# Sheet1.net
KiCad netlist of a schematic drawn in Altium Designer
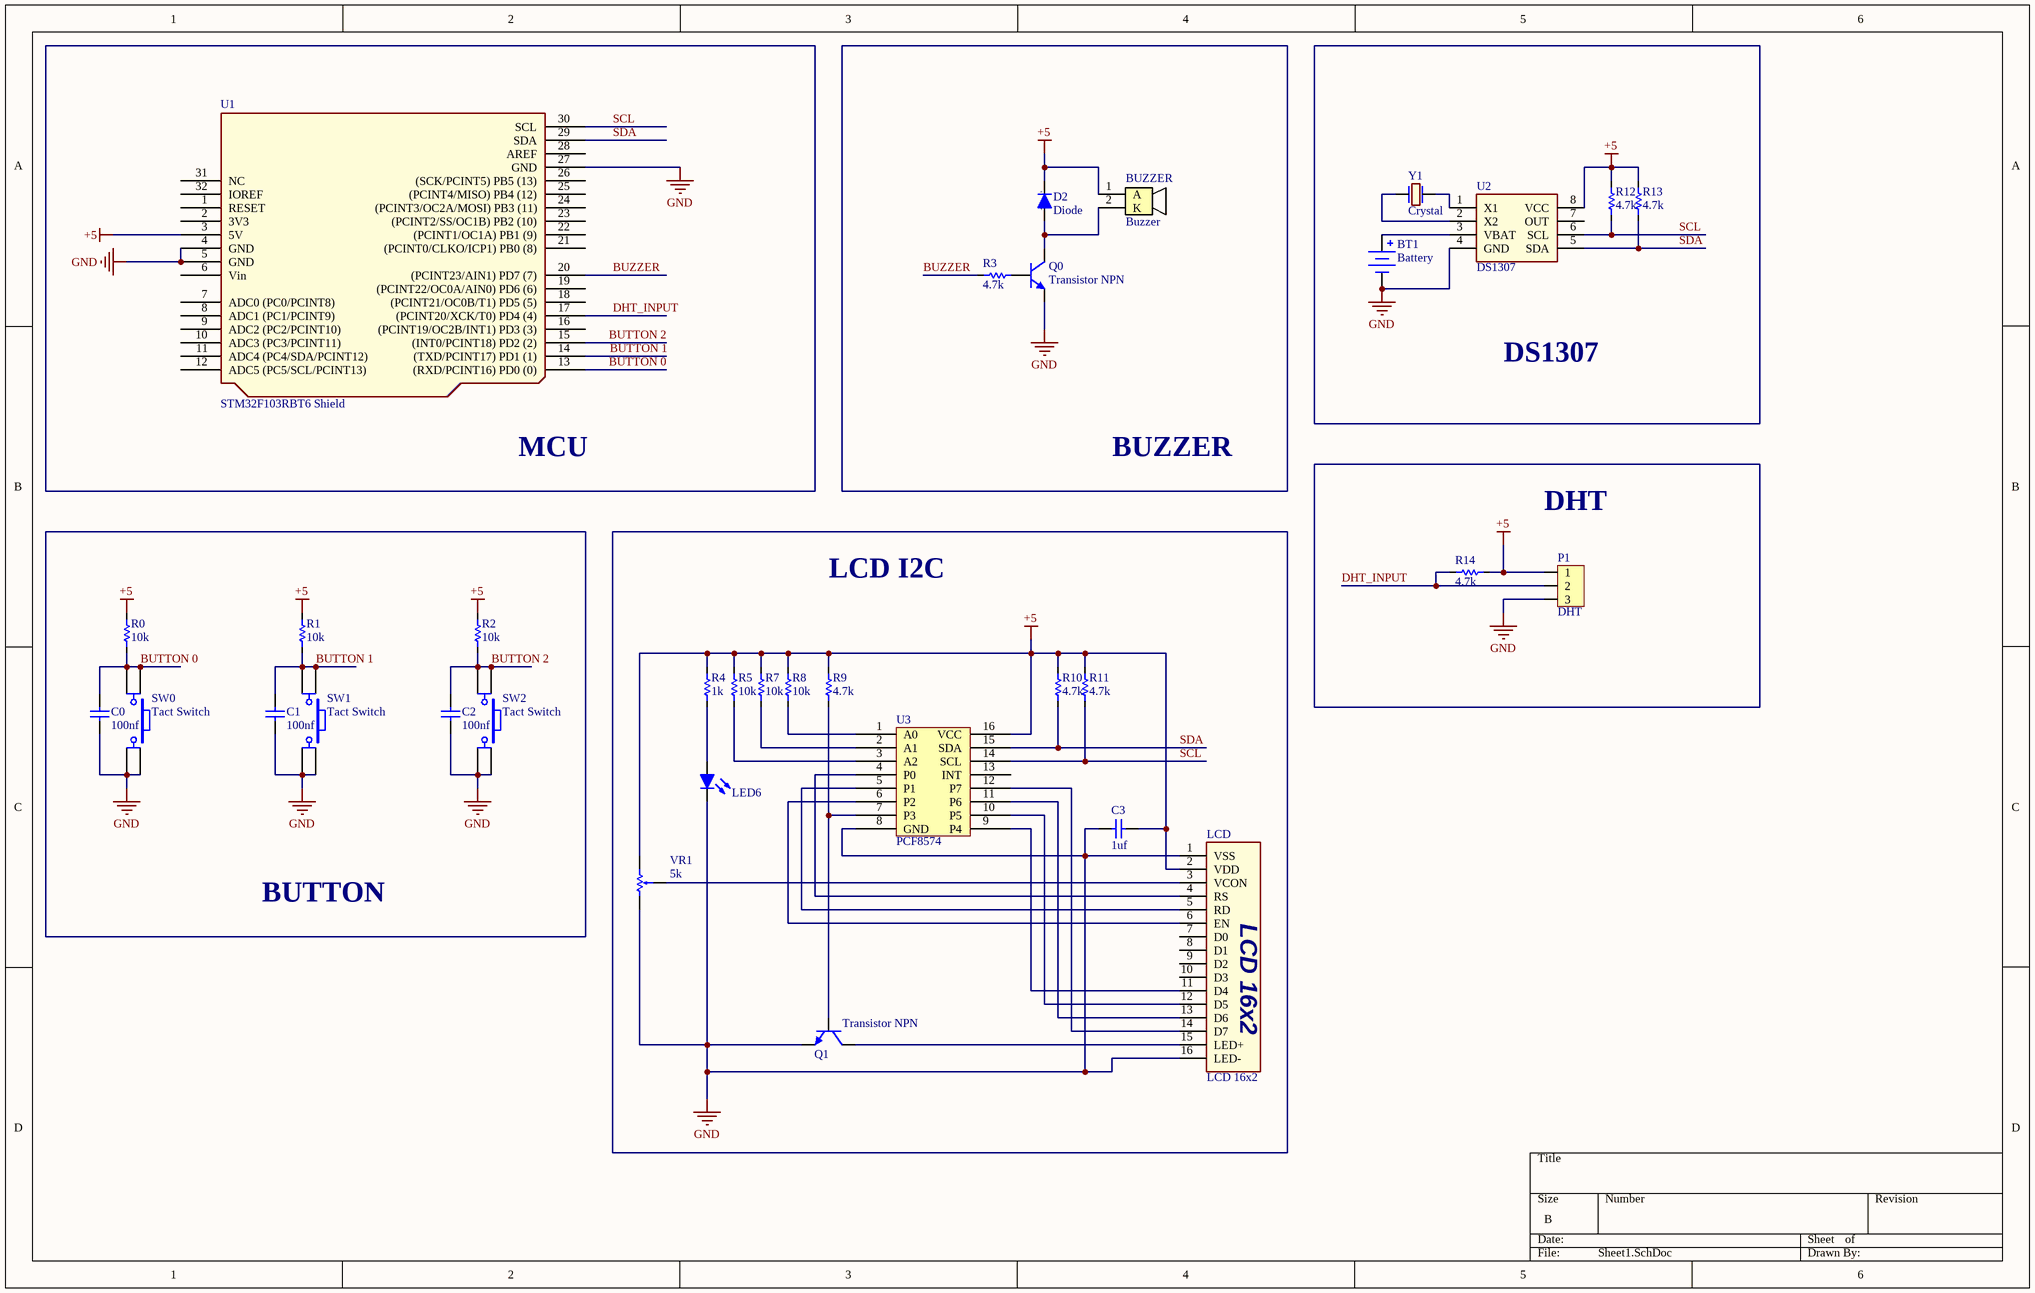
[diagram p0: Sheet1.SchDoc]

(export (version "E")
  (design (tool "Eeschema 10.0.6"))
  (components
    (comp (ref "BT1")
      (value "Battery")
      (footprint "CON CR2032")
      (libsource (lib "BKIT4U_LIB_NEW") (part "Battery"))
    )
    (comp (ref "BUZZER")
      (value "Buzzer")
      (footprint "BUZZER")
      (libsource (lib "BKIT4U_LIB_NEW") (part "Buzzer"))
    )
    (comp (ref "C0")
      (value "100nf")
      (footprint "C 0805 (2012)")
      (description "Capacitor non-pol")
      (libsource (lib "BKIT4U_LIB_NEW") (part "Capacitor NP"))
    )
    (comp (ref "C1")
      (value "100nf")
      (footprint "C 0805 (2012)")
      (description "Capacitor non-pol")
      (libsource (lib "BKIT4U_LIB_NEW") (part "Capacitor NP"))
    )
    (comp (ref "C2")
      (value "100nf")
      (footprint "C 0805 (2012)")
      (description "Capacitor non-pol")
      (libsource (lib "BKIT4U_LIB_NEW") (part "Capacitor NP"))
    )
    (comp (ref "C3")
      (value "1uf")
      (footprint "C 0805 (2012)")
      (description "Capacitor non-pol")
      (libsource (lib "BKIT4U_LIB_NEW") (part "Capacitor NP"))
    )
    (comp (ref "D2")
      (value "Diode")
      (footprint "SOD-80")
      (description "Default Diode")
      (fields (field (name "PUBLISHER") "Altium Limited"))
      (libsource (lib "BKIT4U_LIB_NEW") (part "Diode"))
    )
    (comp (ref "LCD")
      (value "LCD 16x2")
      (footprint "BKIT4U_LIB_NEW:LCD 16x2")
      (description "Character LCD 16x2")
      (libsource (lib "BKIT4U_LIB_NEW") (part "LCD 16x2"))
    )
    (comp (ref "LED6")
      (value "Led")
      (footprint "Led SMD 0805")
      (description "Typical LED")
      (libsource (lib "BKIT4U_LIB_NEW") (part "Led"))
    )
    (comp (ref "P1")
      (value "DHT")
      (footprint "XH2.54-3P")
      (description "Header, 3-Pin")
      (libsource (lib "BKIT4U_LIB_NEW") (part "Header 3"))
    )
    (comp (ref "Q0")
      (value "Transistor NPN")
      (footprint "SOT-23")
      (description "NPN Bipolar Transistor")
      (libsource (lib "BKIT4U_LIB_NEW") (part "Transistor NPN"))
    )
    (comp (ref "Q1")
      (value "Transistor NPN")
      (footprint "SOT-23")
      (description "NPN Bipolar Transistor")
      (libsource (lib "BKIT4U_LIB_NEW") (part "Transistor NPN"))
    )
    (comp (ref "R0")
      (value "10k")
      (footprint "R 0805 (2012)")
      (description "Resistor")
      (fields (field (name "PUBLISHER") "Altium Limited"))
      (libsource (lib "BKIT4U_LIB_NEW") (part "Resistor"))
    )
    (comp (ref "R1")
      (value "10k")
      (footprint "R 0805 (2012)")
      (description "Resistor")
      (fields (field (name "PUBLISHER") "Altium Limited"))
      (libsource (lib "BKIT4U_LIB_NEW") (part "Resistor"))
    )
    (comp (ref "R2")
      (value "10k")
      (footprint "R 0805 (2012)")
      (description "Resistor")
      (fields (field (name "PUBLISHER") "Altium Limited"))
      (libsource (lib "BKIT4U_LIB_NEW") (part "Resistor"))
    )
    (comp (ref "R3")
      (value "4.7k")
      (footprint "R 0805 (2012)")
      (description "Resistor")
      (fields (field (name "PUBLISHER") "Altium Limited"))
      (libsource (lib "BKIT4U_LIB_NEW") (part "Resistor"))
    )
    (comp (ref "R4")
      (value "1k")
      (footprint "R 0805 (2012)")
      (description "Resistor")
      (fields (field (name "PUBLISHER") "Altium Limited"))
      (libsource (lib "BKIT4U_LIB_NEW") (part "Resistor"))
    )
    (comp (ref "R5")
      (value "10k")
      (footprint "R 0805 (2012)")
      (description "Resistor")
      (fields (field (name "PUBLISHER") "Altium Limited"))
      (libsource (lib "BKIT4U_LIB_NEW") (part "Resistor"))
    )
    (comp (ref "R7")
      (value "10k")
      (footprint "R 0805 (2012)")
      (description "Resistor")
      (fields (field (name "PUBLISHER") "Altium Limited"))
      (libsource (lib "BKIT4U_LIB_NEW") (part "Resistor"))
    )
    (comp (ref "R8")
      (value "10k")
      (footprint "R 0805 (2012)")
      (description "Resistor")
      (fields (field (name "PUBLISHER") "Altium Limited"))
      (libsource (lib "BKIT4U_LIB_NEW") (part "Resistor"))
    )
    (comp (ref "R9")
      (value "4.7k")
      (footprint "R 0805 (2012)")
      (description "Resistor")
      (fields (field (name "PUBLISHER") "Altium Limited"))
      (libsource (lib "BKIT4U_LIB_NEW") (part "Resistor"))
    )
    (comp (ref "R10")
      (value "4.7k")
      (footprint "R 0805 (2012)")
      (description "Resistor")
      (fields (field (name "PUBLISHER") "Altium Limited"))
      (libsource (lib "BKIT4U_LIB_NEW") (part "Resistor"))
    )
    (comp (ref "R11")
      (value "4.7k")
      (footprint "R 0805 (2012)")
      (description "Resistor")
      (fields (field (name "PUBLISHER") "Altium Limited"))
      (libsource (lib "BKIT4U_LIB_NEW") (part "Resistor"))
    )
    (comp (ref "R12")
      (value "4.7k")
      (footprint "R 0805 (2012)")
      (description "Resistor")
      (fields (field (name "PUBLISHER") "Altium Limited"))
      (libsource (lib "BKIT4U_LIB_NEW") (part "Resistor"))
    )
    (comp (ref "R13")
      (value "4.7k")
      (footprint "R 0805 (2012)")
      (description "Resistor")
      (fields (field (name "PUBLISHER") "Altium Limited"))
      (libsource (lib "BKIT4U_LIB_NEW") (part "Resistor"))
    )
    (comp (ref "R14")
      (value "4.7k")
      (footprint "R 0805 (2012)")
      (description "Resistor")
      (fields (field (name "PUBLISHER") "Altium Limited"))
      (libsource (lib "BKIT4U_LIB_NEW") (part "Resistor"))
    )
    (comp (ref "SW0")
      (value "Tact Switch")
      (footprint "SW/4/DIP 12x12x7")
      (description "Tact switch 4 pin")
      (libsource (lib "BKIT4U_LIB_NEW") (part "SW SPST-4"))
    )
    (comp (ref "SW1")
      (value "Tact Switch")
      (footprint "SW/4/DIP 12x12x7")
      (description "Tact switch 4 pin")
      (libsource (lib "BKIT4U_LIB_NEW") (part "SW SPST-4"))
    )
    (comp (ref "SW2")
      (value "Tact Switch")
      (footprint "SW/4/DIP 12x12x7")
      (description "Tact switch 4 pin")
      (libsource (lib "BKIT4U_LIB_NEW") (part "SW SPST-4"))
    )
    (comp (ref "U1")
      (value "STM32F103RBT6 Shield")
      (footprint "Arduino Uno R3 Shield 2xPins")
      (description "Arduino Uno R3 shield pins connection")
      (libsource (lib "BKIT4U_LIB_NEW") (part "Arduino Uno R3 shield"))
    )
    (comp (ref "U2") (value "DS1307") (footprint "DIP 8") (libsource (lib "BKIT4U_LIB_NEW") (part "DS1307")))
    (comp (ref "U3")
      (value "PCF8574")
      (footprint "BKIT4U_LIB_NEW:SOIC-16")
      (description "Remote 8-Bit I/O Expander for I  2C Bus")
      (libsource (lib "Custom Library") (part "PCF8574"))
    )
    (comp (ref "VR1")
      (value "5k")
      (footprint "R Var 3mm")
      (description "Resistor Variable")
      (libsource (lib "chipfc_libs") (part "Resistor Variable"))
    )
    (comp (ref "Y1")
      (value "Crystal")
      (footprint "Crystal HC49US SMD")
      (libsource (lib "BKIT4U_LIB_NEW") (part "Crystal"))
    )
  )
  (nets
    (net (code "1") (name "+5") (class "Default")
      (node (ref "BUZZER") (pin "1") (pinfunction "A_1") (pintype "passive"))
      (node (ref "C3") (pin "2") (pinfunction "2_2") (pintype "passive"))
      (node (ref "D2") (pin "1") (pinfunction "Cathode_1") (pintype "passive"))
      (node (ref "LCD") (pin "2") (pinfunction "VDD_2") (pintype "passive"))
      (node (ref "P1") (pin "1") (pinfunction "1_1") (pintype "passive"))
      (node (ref "R0") (pin "2") (pinfunction "2_2") (pintype "passive"))
      (node (ref "R1") (pin "2") (pinfunction "2_2") (pintype "passive"))
      (node (ref "R10") (pin "2") (pinfunction "2_2") (pintype "passive"))
      (node (ref "R11") (pin "2") (pinfunction "2_2") (pintype "passive"))
      (node (ref "R12") (pin "2") (pinfunction "2_2") (pintype "passive"))
      (node (ref "R13") (pin "2") (pinfunction "2_2") (pintype "passive"))
      (node (ref "R14") (pin "1") (pinfunction "1_1") (pintype "passive"))
      (node (ref "R2") (pin "2") (pinfunction "2_2") (pintype "passive"))
      (node (ref "R4") (pin "2") (pinfunction "2_2") (pintype "passive"))
      (node (ref "R5") (pin "2") (pinfunction "2_2") (pintype "passive"))
      (node (ref "R7") (pin "2") (pinfunction "2_2") (pintype "passive"))
      (node (ref "R8") (pin "2") (pinfunction "2_2") (pintype "passive"))
      (node (ref "R9") (pin "2") (pinfunction "2_2") (pintype "passive"))
      (node (ref "U1") (pin "3") (pinfunction "5V_3") (pintype "passive"))
      (node (ref "U2") (pin "8") (pinfunction "VCC_8") (pintype "passive"))
      (node (ref "U3") (pin "16") (pinfunction "VCC_16") (pintype "passive"))
      (node (ref "VR1") (pin "1") (pinfunction "1_1") (pintype "passive"))
    )
    (net (code "2") (name "/BUTTON 0") (class "Default")
      (node (ref "C0") (pin "1") (pinfunction "1_1") (pintype "passive"))
      (node (ref "R0") (pin "1") (pinfunction "1_1") (pintype "passive"))
      (node (ref "SW0") (pin "1") (pinfunction "1_1") (pintype "passive"))
      (node (ref "SW0") (pin "4") (pinfunction "2_4") (pintype "passive"))
      (node (ref "U1") (pin "13") (pinfunction "(RXD/PCINT16)_PD0_(0)_13") (pintype "passive"))
    )
    (net (code "3") (name "/BUTTON 1") (class "Default")
      (node (ref "C1") (pin "1") (pinfunction "1_1") (pintype "passive"))
      (node (ref "R1") (pin "1") (pinfunction "1_1") (pintype "passive"))
      (node (ref "SW1") (pin "1") (pinfunction "1_1") (pintype "passive"))
      (node (ref "SW1") (pin "4") (pinfunction "2_4") (pintype "passive"))
      (node (ref "U1") (pin "14") (pinfunction "(TXD/PCINT17)_PD1_(1)_14") (pintype "passive"))
    )
    (net (code "4") (name "/BUTTON 2") (class "Default")
      (node (ref "C2") (pin "1") (pinfunction "1_1") (pintype "passive"))
      (node (ref "R2") (pin "1") (pinfunction "1_1") (pintype "passive"))
      (node (ref "SW2") (pin "1") (pinfunction "1_1") (pintype "passive"))
      (node (ref "SW2") (pin "4") (pinfunction "2_4") (pintype "passive"))
      (node (ref "U1") (pin "15") (pinfunction "(INT0/PCINT18)_PD2_(2)_15") (pintype "passive"))
    )
    (net (code "5") (name "/BUZZER") (class "Default")
      (node (ref "R3") (pin "1") (pinfunction "1_1") (pintype "passive"))
      (node (ref "U1") (pin "20") (pinfunction "(PCINT23/AIN1)_PD7_(7)_20") (pintype "passive"))
    )
    (net (code "6") (name "/DHT_INPUT") (class "Default")
      (node (ref "P1") (pin "2") (pinfunction "2_2") (pintype "passive"))
      (node (ref "R14") (pin "2") (pinfunction "2_2") (pintype "passive"))
      (node (ref "U1") (pin "17") (pinfunction "(PCINT20/XCK/T0)_PD4_(4)_17") (pintype "passive"))
    )
    (net (code "7") (name "/SCL") (class "Default")
      (node (ref "R11") (pin "1") (pinfunction "1_1") (pintype "passive"))
      (node (ref "R12") (pin "1") (pinfunction "1_1") (pintype "passive"))
      (node (ref "U1") (pin "30") (pinfunction "SCL_30") (pintype "passive"))
      (node (ref "U2") (pin "6") (pinfunction "SCL_6") (pintype "passive"))
      (node (ref "U3") (pin "14") (pinfunction "SCL_14") (pintype "passive"))
    )
    (net (code "8") (name "/SDA") (class "Default")
      (node (ref "R10") (pin "1") (pinfunction "1_1") (pintype "passive"))
      (node (ref "R13") (pin "1") (pinfunction "1_1") (pintype "passive"))
      (node (ref "U1") (pin "29") (pinfunction "SDA_29") (pintype "passive"))
      (node (ref "U2") (pin "5") (pinfunction "SDA_5") (pintype "passive"))
      (node (ref "U3") (pin "15") (pinfunction "SDA_15") (pintype "passive"))
    )
    (net (code "9") (name "GND") (class "Default")
      (node (ref "BT1") (pin "2") (pinfunction "GND_2") (pintype "passive"))
      (node (ref "C0") (pin "2") (pinfunction "2_2") (pintype "passive"))
      (node (ref "C1") (pin "2") (pinfunction "2_2") (pintype "passive"))
      (node (ref "C2") (pin "2") (pinfunction "2_2") (pintype "passive"))
      (node (ref "C3") (pin "1") (pinfunction "1_1") (pintype "passive"))
      (node (ref "LCD") (pin "1") (pinfunction "VSS_1") (pintype "passive"))
      (node (ref "LCD") (pin "16") (pinfunction "LED-_16") (pintype "passive"))
      (node (ref "LED6") (pin "1") (pinfunction "K_1") (pintype "passive"))
      (node (ref "P1") (pin "3") (pinfunction "3_3") (pintype "passive"))
      (node (ref "Q0") (pin "2") (pinfunction "E_2") (pintype "passive"))
      (node (ref "Q1") (pin "2") (pinfunction "E_2") (pintype "passive"))
      (node (ref "SW0") (pin "2") (pinfunction "2_2") (pintype "passive"))
      (node (ref "SW0") (pin "3") (pinfunction "1_3") (pintype "passive"))
      (node (ref "SW1") (pin "2") (pinfunction "2_2") (pintype "passive"))
      (node (ref "SW1") (pin "3") (pinfunction "1_3") (pintype "passive"))
      (node (ref "SW2") (pin "2") (pinfunction "2_2") (pintype "passive"))
      (node (ref "SW2") (pin "3") (pinfunction "1_3") (pintype "passive"))
      (node (ref "U1") (pin "27") (pinfunction "GND_27") (pintype "power_in"))
      (node (ref "U1") (pin "4") (pinfunction "GND_4") (pintype "power_in"))
      (node (ref "U1") (pin "5") (pinfunction "GND_5") (pintype "power_in"))
      (node (ref "U2") (pin "4") (pinfunction "GND_4") (pintype "passive"))
      (node (ref "U3") (pin "8") (pinfunction "GND_8") (pintype "passive"))
      (node (ref "VR1") (pin "3") (pinfunction "3_3") (pintype "passive"))
    )
    (net (code "10") (name "Net-(BT1-VCC)") (class "Default")
      (node (ref "BT1") (pin "1") (pinfunction "VCC_1") (pintype "passive"))
      (node (ref "U2") (pin "3") (pinfunction "VBAT_3") (pintype "passive"))
    )
    (net (code "11") (name "Net-(BUZZER-K)") (class "Default")
      (node (ref "BUZZER") (pin "2") (pinfunction "K_2") (pintype "passive"))
      (node (ref "D2") (pin "2") (pinfunction "Anode_2") (pintype "passive"))
      (node (ref "Q0") (pin "3") (pinfunction "C_3") (pintype "passive"))
    )
    (net (code "12") (name "Net-(LCD-D4)") (class "Default")
      (node (ref "LCD") (pin "11") (pinfunction "D4_11") (pintype "passive"))
      (node (ref "U3") (pin "9") (pinfunction "P4_9") (pintype "passive"))
    )
    (net (code "13") (name "Net-(LCD-D5)") (class "Default")
      (node (ref "LCD") (pin "12") (pinfunction "D5_12") (pintype "passive"))
      (node (ref "U3") (pin "10") (pinfunction "P5_10") (pintype "passive"))
    )
    (net (code "14") (name "Net-(LCD-D6)") (class "Default")
      (node (ref "LCD") (pin "13") (pinfunction "D6_13") (pintype "passive"))
      (node (ref "U3") (pin "11") (pinfunction "P6_11") (pintype "passive"))
    )
    (net (code "15") (name "Net-(LCD-D7)") (class "Default")
      (node (ref "LCD") (pin "14") (pinfunction "D7_14") (pintype "passive"))
      (node (ref "U3") (pin "12") (pinfunction "P7_12") (pintype "passive"))
    )
    (net (code "16") (name "Net-(LCD-EN)") (class "Default")
      (node (ref "LCD") (pin "6") (pinfunction "EN_6") (pintype "passive"))
      (node (ref "U3") (pin "6") (pinfunction "P2_6") (pintype "passive"))
    )
    (net (code "17") (name "Net-(LCD-LED+)") (class "Default")
      (node (ref "LCD") (pin "15") (pinfunction "LED+_15") (pintype "passive"))
      (node (ref "Q1") (pin "3") (pinfunction "C_3") (pintype "passive"))
    )
    (net (code "18") (name "Net-(LCD-RD)") (class "Default")
      (node (ref "LCD") (pin "5") (pinfunction "RD_5") (pintype "passive"))
      (node (ref "U3") (pin "5") (pinfunction "P1_5") (pintype "passive"))
    )
    (net (code "19") (name "Net-(LCD-RS)") (class "Default")
      (node (ref "LCD") (pin "4") (pinfunction "RS_4") (pintype "passive"))
      (node (ref "U3") (pin "4") (pinfunction "P0_4") (pintype "passive"))
    )
    (net (code "20") (name "Net-(LCD-VCON)") (class "Default")
      (node (ref "LCD") (pin "3") (pinfunction "VCON_3") (pintype "passive"))
      (node (ref "VR1") (pin "2") (pinfunction "2_2") (pintype "passive"))
    )
    (net (code "21") (name "Net-(LED6-A)") (class "Default")
      (node (ref "LED6") (pin "2") (pinfunction "A_2") (pintype "passive"))
      (node (ref "R4") (pin "1") (pinfunction "1_1") (pintype "passive"))
    )
    (net (code "22") (name "Net-(Q0-B)") (class "Default")
      (node (ref "Q0") (pin "1") (pinfunction "B_1") (pintype "passive"))
      (node (ref "R3") (pin "2") (pinfunction "2_2") (pintype "passive"))
    )
    (net (code "23") (name "Net-(Q1-B)") (class "Default")
      (node (ref "Q1") (pin "1") (pinfunction "B_1") (pintype "passive"))
      (node (ref "R9") (pin "1") (pinfunction "1_1") (pintype "passive"))
      (node (ref "U3") (pin "7") (pinfunction "P3_7") (pintype "passive"))
    )
    (net (code "24") (name "Net-(U2-X1)") (class "Default")
      (node (ref "U2") (pin "1") (pinfunction "X1_1") (pintype "passive"))
      (node (ref "Y1") (pin "2") (pinfunction "2_2") (pintype "passive"))
    )
    (net (code "25") (name "Net-(U2-X2)") (class "Default")
      (node (ref "U2") (pin "2") (pinfunction "X2_2") (pintype "passive"))
      (node (ref "Y1") (pin "1") (pinfunction "1_1") (pintype "passive"))
    )
    (net (code "26") (name "Net-(U3-A0)") (class "Default")
      (node (ref "R8") (pin "1") (pinfunction "1_1") (pintype "passive"))
      (node (ref "U3") (pin "1") (pinfunction "A0_1") (pintype "passive"))
    )
    (net (code "27") (name "Net-(U3-A1)") (class "Default")
      (node (ref "R7") (pin "1") (pinfunction "1_1") (pintype "passive"))
      (node (ref "U3") (pin "2") (pinfunction "A1_2") (pintype "passive"))
    )
    (net (code "28") (name "Net-(U3-A2)") (class "Default")
      (node (ref "R5") (pin "1") (pinfunction "1_1") (pintype "passive"))
      (node (ref "U3") (pin "3") (pinfunction "A2_3") (pintype "passive"))
    )
    (net (code "29") (name "unconnected-(LCD-D0-Pad7)") (class "Default")
      (node (ref "LCD") (pin "7") (pinfunction "D0_7") (pintype "passive"))
    )
    (net (code "30") (name "unconnected-(LCD-D1-Pad8)") (class "Default")
      (node (ref "LCD") (pin "8") (pinfunction "D1_8") (pintype "passive"))
    )
    (net (code "31") (name "unconnected-(LCD-D2-Pad9)") (class "Default")
      (node (ref "LCD") (pin "9") (pinfunction "D2_9") (pintype "passive"))
    )
    (net (code "32") (name "unconnected-(LCD-D3-Pad10)") (class "Default")
      (node (ref "LCD") (pin "10") (pinfunction "D3_10") (pintype "passive"))
    )
    (net (code "33") (name "unconnected-(U1-(PCINT0{slash}CLKO{slash}ICP1)_PB0_(8)-Pad21)") (class "Default")
      (node (ref "U1") (pin "21") (pinfunction "(PCINT0/CLKO/ICP1)_PB0_(8)_21") (pintype "passive"))
    )
    (net (code "34") (name "unconnected-(U1-(PCINT1{slash}OC1A)_PB1_(9)-Pad22)") (class "Default")
      (node (ref "U1") (pin "22") (pinfunction "(PCINT1/OC1A)_PB1_(9)_22") (pintype "passive"))
    )
    (net (code "35") (name "unconnected-(U1-(PCINT2{slash}SS{slash}OC1B)_PB2_(10)-Pad23)") (class "Default")
      (node (ref "U1") (pin "23") (pinfunction "(PCINT2/SS/OC1B)_PB2_(10)_23") (pintype "passive"))
    )
    (net (code "36") (name "unconnected-(U1-(PCINT3{slash}OC2A{slash}MOSI)_PB3_(11)-Pad24)") (class "Default")
      (node (ref "U1") (pin "24") (pinfunction "(PCINT3/OC2A/MOSI)_PB3_(11)_24") (pintype "passive"))
    )
    (net (code "37") (name "unconnected-(U1-(PCINT4{slash}MISO)_PB4_(12)-Pad25)") (class "Default")
      (node (ref "U1") (pin "25") (pinfunction "(PCINT4/MISO)_PB4_(12)_25") (pintype "passive"))
    )
    (net (code "38") (name "unconnected-(U1-(PCINT19{slash}OC2B{slash}INT1)_PD3_(3)-Pad16)") (class "Default")
      (node (ref "U1") (pin "16") (pinfunction "(PCINT19/OC2B/INT1)_PD3_(3)_16") (pintype "passive"))
    )
    (net (code "39") (name "unconnected-(U1-(PCINT21{slash}OC0B{slash}T1)_PD5_(5)-Pad18)") (class "Default")
      (node (ref "U1") (pin "18") (pinfunction "(PCINT21/OC0B/T1)_PD5_(5)_18") (pintype "passive"))
    )
    (net (code "40") (name "unconnected-(U1-(PCINT22{slash}OC0A{slash}AIN0)_PD6_(6)-Pad19)") (class "Default")
      (node (ref "U1") (pin "19") (pinfunction "(PCINT22/OC0A/AIN0)_PD6_(6)_19") (pintype "passive"))
    )
    (net (code "41") (name "unconnected-(U1-(SCK{slash}PCINT5)_PB5_(13)-Pad26)") (class "Default")
      (node (ref "U1") (pin "26") (pinfunction "(SCK/PCINT5)_PB5_(13)_26") (pintype "passive"))
    )
    (net (code "42") (name "unconnected-(U1-3V3-Pad2)") (class "Default")
      (node (ref "U1") (pin "2") (pinfunction "3V3_2") (pintype "passive"))
    )
    (net (code "43") (name "unconnected-(U1-ADC0_(PC0{slash}PCINT8)-Pad7)") (class "Default")
      (node (ref "U1") (pin "7") (pinfunction "ADC0_(PC0/PCINT8)_7") (pintype "passive"))
    )
    (net (code "44") (name "unconnected-(U1-ADC1_(PC1{slash}PCINT9)-Pad8)") (class "Default")
      (node (ref "U1") (pin "8") (pinfunction "ADC1_(PC1/PCINT9)_8") (pintype "passive"))
    )
    (net (code "45") (name "unconnected-(U1-ADC2_(PC2{slash}PCINT10)-Pad9)") (class "Default")
      (node (ref "U1") (pin "9") (pinfunction "ADC2_(PC2/PCINT10)_9") (pintype "passive"))
    )
    (net (code "46") (name "unconnected-(U1-ADC3_(PC3{slash}PCINT11)-Pad10)") (class "Default")
      (node (ref "U1") (pin "10") (pinfunction "ADC3_(PC3/PCINT11)_10") (pintype "passive"))
    )
    (net (code "47") (name "unconnected-(U1-ADC4_(PC4{slash}SDA{slash}PCINT12)-Pad11)") (class "Default")
      (node (ref "U1") (pin "11") (pinfunction "ADC4_(PC4/SDA/PCINT12)_11") (pintype "passive"))
    )
    (net (code "48") (name "unconnected-(U1-ADC5_(PC5{slash}SCL{slash}PCINT13)-Pad12)") (class "Default")
      (node (ref "U1") (pin "12") (pinfunction "ADC5_(PC5/SCL/PCINT13)_12") (pintype "passive"))
    )
    (net (code "49") (name "unconnected-(U1-AREF-Pad28)") (class "Default")
      (node (ref "U1") (pin "28") (pinfunction "AREF_28") (pintype "passive"))
    )
    (net (code "50") (name "unconnected-(U1-IOREF-Pad32)") (class "Default")
      (node (ref "U1") (pin "32") (pinfunction "IOREF_32") (pintype "passive"))
    )
    (net (code "51") (name "unconnected-(U1-NC-Pad31)") (class "Default")
      (node (ref "U1") (pin "31") (pinfunction "NC_31") (pintype "passive"))
    )
    (net (code "52") (name "unconnected-(U1-RESET-Pad1)") (class "Default")
      (node (ref "U1") (pin "1") (pinfunction "RESET_1") (pintype "passive"))
    )
    (net (code "53") (name "unconnected-(U1-Vin-Pad6)") (class "Default")
      (node (ref "U1") (pin "6") (pinfunction "Vin_6") (pintype "passive"))
    )
    (net (code "54") (name "unconnected-(U2-OUT-Pad7)") (class "Default")
      (node (ref "U2") (pin "7") (pinfunction "OUT_7") (pintype "passive"))
    )
    (net (code "55") (name "unconnected-(U3-INT-Pad13)") (class "Default")
      (node (ref "U3") (pin "13") (pinfunction "INT_13") (pintype "passive"))
    )
  )
)
